# olm-flora-sqw-noRTC.net
KiCad netlist of a schematic drawn in EAGLE
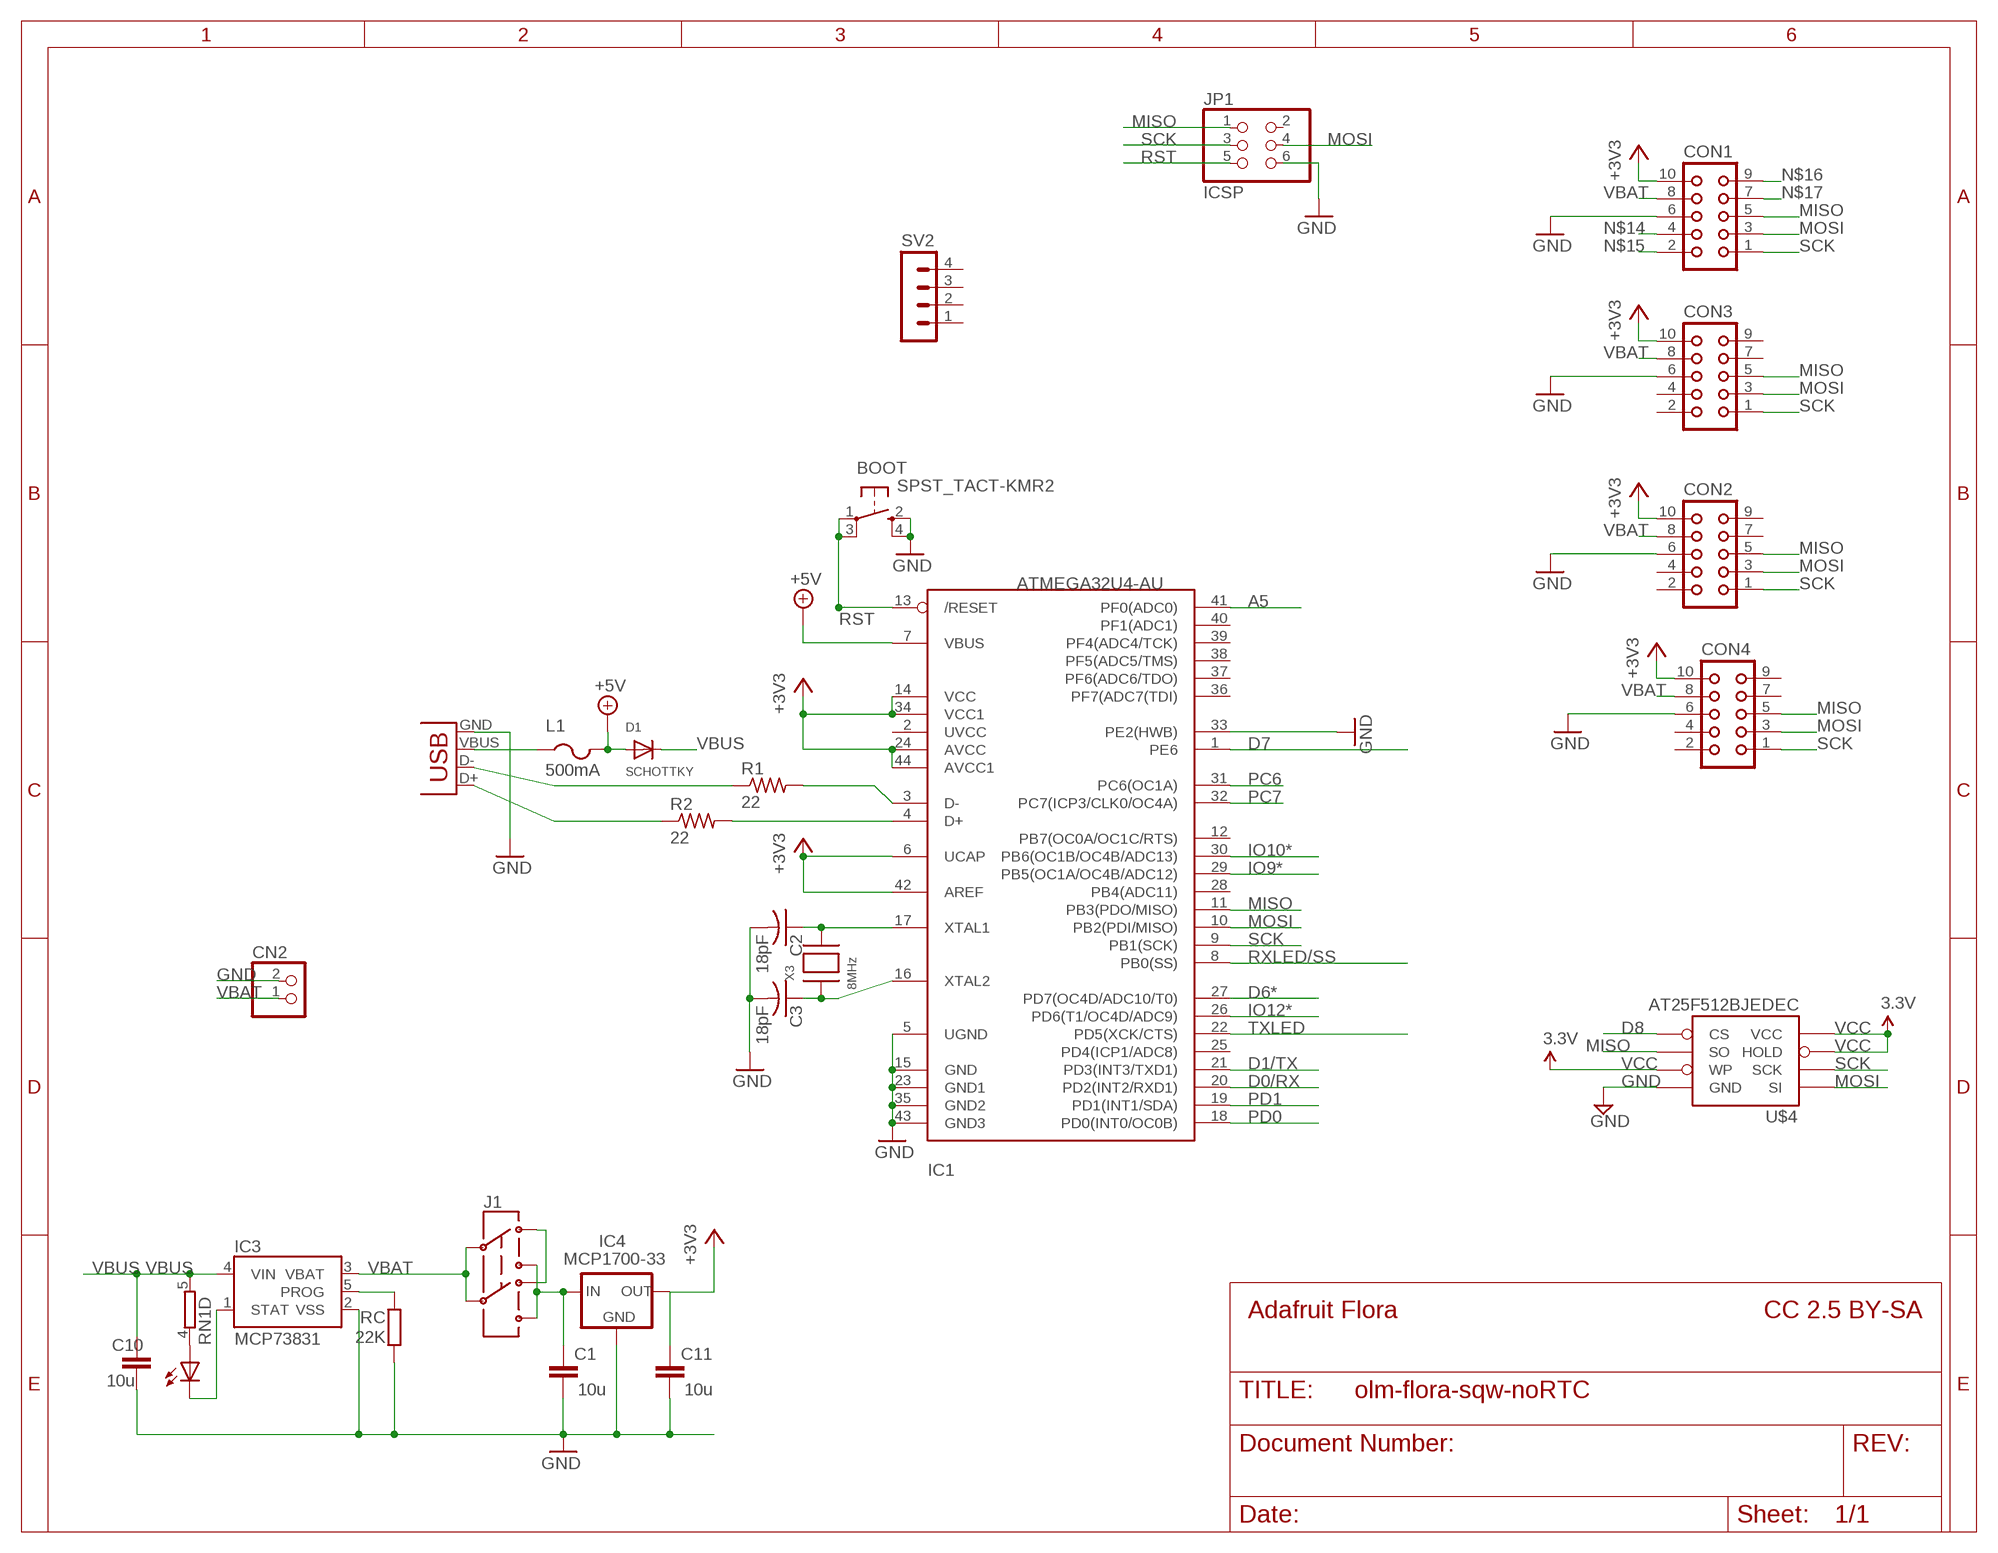
[diagram p0: schematic, sheet 1]

(export (version "E")
  (design (tool "Eeschema 10.0.6"))
  (components
    (comp (ref "BOOT")
      (value "SPST_TACT-KMR2")
      (footprint "eagle-import:KMR2")
      (libsource (lib "eagle-import") (part "SPST_TACT-KMR2"))
    )
    (comp (ref "C1")
      (value "10u")
      (footprint "eagle-import:C0805")
      (libsource (lib "eagle-import") (part "C-EUC0805"))
    )
    (comp (ref "C2")
      (value "18pF")
      (footprint "eagle-import:C0805K")
      (libsource (lib "eagle-import") (part "C-USC0805K"))
    )
    (comp (ref "C3")
      (value "18pF")
      (footprint "eagle-import:C0805K")
      (libsource (lib "eagle-import") (part "C-USC0805K"))
    )
    (comp (ref "C10")
      (value "10u")
      (footprint "eagle-import:C0805")
      (libsource (lib "eagle-import") (part "C-EUC0805"))
    )
    (comp (ref "C11")
      (value "10u")
      (footprint "eagle-import:C0805")
      (libsource (lib "eagle-import") (part "C-EUC0805"))
    )
    (comp (ref "CHG")
      (value "0805")
      (footprint "eagle-import:CHIPLED_0805")
      (libsource (lib "eagle-import") (part "LEDCHIPLED_0805"))
    )
    (comp (ref "CN2")
      (value "JST_2PIN-SMT-RA")
      (footprint "eagle-import:JST-PH-2-SMT-RA")
      (libsource (lib "eagle-import") (part "JST_2PIN-SMT-RA"))
    )
    (comp (ref "CON1")
      (value "CON10")
      (footprint "eagle-import:CON10")
      (libsource (lib "eagle-import") (part "CON10"))
    )
    (comp (ref "CON2")
      (value "CON10")
      (footprint "eagle-import:CON10")
      (libsource (lib "eagle-import") (part "CON10"))
    )
    (comp (ref "CON3")
      (value "CON10")
      (footprint "eagle-import:CON10")
      (libsource (lib "eagle-import") (part "CON10"))
    )
    (comp (ref "CON4")
      (value "CON10")
      (footprint "eagle-import:CON10")
      (libsource (lib "eagle-import") (part "CON10"))
    )
    (comp (ref "D1")
      (value "SCHOTTKY")
      (footprint "eagle-import:SOD-123")
      (libsource (lib "eagle-import") (part "DIODESOD-123"))
    )
    (comp (ref "IC1")
      (value "ATMEGA32U4-AU")
      (footprint "eagle-import:TQFP44")
      (libsource (lib "eagle-import") (part "ATMEGA32U4-AU"))
    )
    (comp (ref "IC3")
      (value "MCP73831")
      (footprint "eagle-import:SOT23-5")
      (libsource (lib "eagle-import") (part "MCP73831"))
    )
    (comp (ref "IC4")
      (value "MCP1700-33")
      (footprint "eagle-import:SOT23")
      (libsource (lib "eagle-import") (part "MCP1700SOT233"))
    )
    (comp (ref "J1")
      (value "AYZ0202")
      (footprint "eagle-import:AYZ0202")
      (libsource (lib "eagle-import") (part "AYZ0202"))
    )
    (comp (ref "JP1")
      (value "ICSP")
      (footprint "eagle-import:2X03")
      (libsource (lib "eagle-import") (part "PINHD-2X3"))
    )
    (comp (ref "L1")
      (value "500mA")
      (footprint "eagle-import:R1206")
      (libsource (lib "eagle-import") (part "PTCFUSE-1206"))
    )
    (comp (ref "R1")
      (value "22")
      (footprint "eagle-import:R0805")
      (libsource (lib "eagle-import") (part "R-US_R0805"))
    )
    (comp (ref "R2")
      (value "22")
      (footprint "eagle-import:R0805")
      (libsource (lib "eagle-import") (part "R-US_R0805"))
    )
    (comp (ref "RC")
      (value "22K")
      (footprint "eagle-import:R0805")
      (libsource (lib "eagle-import") (part "R-EU_R0805"))
    )
    (comp (ref "RN1")
      (value "4R-NEXB38V")
      (footprint "eagle-import:EXB38V")
      (libsource (lib "eagle-import") (part "4R-NEXB38V"))
    )
    (comp (ref "SV2")
      (value "MA04-1")
      (footprint "eagle-import:MA04-1")
      (libsource (lib "eagle-import") (part "MA04-1"))
    )
    (comp (ref "U$4")
      (value "AT25F512BJEDEC")
      (footprint "eagle-import:SO08")
      (libsource (lib "eagle-import") (part "AT25F512BJEDEC"))
    )
    (comp (ref "X1")
      (value "USBSMD")
      (footprint "eagle-import:USB-MINIB")
      (libsource (lib "eagle-import") (part "USBSMD"))
    )
    (comp (ref "X3")
      (value "8MHz")
      (footprint "eagle-import:NX5032")
      (libsource (lib "eagle-import") (part "XTALNX5032"))
    )
  )
  (nets
    (net (code "1") (name "+3V3") (class "Default")
      (node (ref "C11") (pin "1") (pinfunction "1_1") (pintype "passive"))
      (node (ref "CON1") (pin "10") (pinfunction "10_10") (pintype "passive"))
      (node (ref "CON2") (pin "10") (pinfunction "10_10") (pintype "passive"))
      (node (ref "CON3") (pin "10") (pinfunction "10_10") (pintype "passive"))
      (node (ref "CON4") (pin "10") (pinfunction "10_10") (pintype "passive"))
      (node (ref "IC1") (pin "14") (pinfunction "VCC_14") (pintype "bidirectional"))
      (node (ref "IC1") (pin "24") (pinfunction "AVCC_24") (pintype "bidirectional"))
      (node (ref "IC1") (pin "34") (pinfunction "VCC1_34") (pintype "bidirectional"))
      (node (ref "IC1") (pin "42") (pinfunction "AREF_42") (pintype "bidirectional"))
      (node (ref "IC1") (pin "44") (pinfunction "AVCC1_44") (pintype "bidirectional"))
      (node (ref "IC1") (pin "6") (pinfunction "UCAP_6") (pintype "bidirectional"))
      (node (ref "IC4") (pin "2") (pinfunction "OUT_2") (pintype "passive"))
    )
    (net (code "2") (name "+5V") (class "Default")
      (node (ref "D1") (pin "A") (pinfunction "A_A") (pintype "passive"))
      (node (ref "IC1") (pin "7") (pinfunction "VBUS_7") (pintype "bidirectional"))
      (node (ref "L1") (pin "2") (pinfunction "2_2") (pintype "passive"))
    )
    (net (code "3") (name "/A5") (class "Default")
      (node (ref "IC1") (pin "41") (pinfunction "PF0(ADC0)_41") (pintype "bidirectional"))
    )
    (net (code "4") (name "/D0{slash}RX") (class "Default")
      (node (ref "IC1") (pin "20") (pinfunction "PD2(INT2/RXD1)_20") (pintype "bidirectional"))
    )
    (net (code "5") (name "/D1{slash}TX") (class "Default")
      (node (ref "IC1") (pin "21") (pinfunction "PD3(INT3/TXD1)_21") (pintype "bidirectional"))
    )
    (net (code "6") (name "/D6*") (class "Default")
      (node (ref "IC1") (pin "27") (pinfunction "PD7(OC4D/ADC10/T0)_27") (pintype "bidirectional"))
    )
    (net (code "7") (name "/D7") (class "Default")
      (node (ref "IC1") (pin "1") (pinfunction "PE6_1") (pintype "bidirectional"))
    )
    (net (code "8") (name "/D8") (class "Default")
      (node (ref "U$4") (pin "1_CS") (pinfunction "CS_1_CS") (pintype "bidirectional"))
    )
    (net (code "9") (name "/IO9*") (class "Default")
      (node (ref "IC1") (pin "29") (pinfunction "PB5(OC1A/OC4B/ADC12)_29") (pintype "bidirectional"))
    )
    (net (code "10") (name "/IO10*") (class "Default")
      (node (ref "IC1") (pin "30") (pinfunction "PB6(OC1B/OC4B/ADC13)_30") (pintype "bidirectional"))
    )
    (net (code "11") (name "/IO12*") (class "Default")
      (node (ref "IC1") (pin "26") (pinfunction "PD6(T1/OC4D/ADC9)_26") (pintype "bidirectional"))
    )
    (net (code "12") (name "/MISO") (class "Default")
      (node (ref "CON1") (pin "5") (pinfunction "5_5") (pintype "passive"))
      (node (ref "CON2") (pin "5") (pinfunction "5_5") (pintype "passive"))
      (node (ref "CON3") (pin "5") (pinfunction "5_5") (pintype "passive"))
      (node (ref "CON4") (pin "5") (pinfunction "5_5") (pintype "passive"))
      (node (ref "IC1") (pin "11") (pinfunction "PB3(PDO/MISO)_11") (pintype "bidirectional"))
      (node (ref "JP1") (pin "1") (pinfunction "1_1") (pintype "passive"))
      (node (ref "U$4") (pin "2_SO") (pinfunction "SO_2_SO") (pintype "bidirectional"))
    )
    (net (code "13") (name "/MOSI") (class "Default")
      (node (ref "CON1") (pin "3") (pinfunction "3_3") (pintype "passive"))
      (node (ref "CON2") (pin "3") (pinfunction "3_3") (pintype "passive"))
      (node (ref "CON3") (pin "3") (pinfunction "3_3") (pintype "passive"))
      (node (ref "CON4") (pin "3") (pinfunction "3_3") (pintype "passive"))
      (node (ref "IC1") (pin "10") (pinfunction "PB2(PDI/MISO)_10") (pintype "bidirectional"))
      (node (ref "JP1") (pin "4") (pinfunction "4_4") (pintype "passive"))
      (node (ref "U$4") (pin "5_SI") (pinfunction "SI_5_SI") (pintype "bidirectional"))
    )
    (net (code "14") (name "/N$14") (class "Default")
      (node (ref "CON1") (pin "4") (pinfunction "4_4") (pintype "passive"))
    )
    (net (code "15") (name "/N$15") (class "Default")
      (node (ref "CON1") (pin "2") (pinfunction "2_2") (pintype "passive"))
    )
    (net (code "16") (name "/N$16") (class "Default")
      (node (ref "CON1") (pin "9") (pinfunction "9_9") (pintype "passive"))
    )
    (net (code "17") (name "/N$17") (class "Default")
      (node (ref "CON1") (pin "7") (pinfunction "7_7") (pintype "passive"))
    )
    (net (code "18") (name "/PC6") (class "Default")
      (node (ref "IC1") (pin "31") (pinfunction "PC6(OC1A)_31") (pintype "bidirectional"))
    )
    (net (code "19") (name "/PC7") (class "Default")
      (node (ref "IC1") (pin "32") (pinfunction "PC7(ICP3/CLK0/OC4A)_32") (pintype "bidirectional"))
    )
    (net (code "20") (name "/PD0") (class "Default")
      (node (ref "IC1") (pin "18") (pinfunction "PD0(INT0/OC0B)_18") (pintype "bidirectional"))
    )
    (net (code "21") (name "/PD1") (class "Default")
      (node (ref "IC1") (pin "19") (pinfunction "PD1(INT1/SDA)_19") (pintype "bidirectional"))
    )
    (net (code "22") (name "/RST") (class "Default")
      (node (ref "BOOT") (pin "1") (pinfunction "P_1") (pintype "passive"))
      (node (ref "BOOT") (pin "3") (pinfunction "P1_3") (pintype "passive"))
      (node (ref "IC1") (pin "13") (pinfunction "/RESET_13") (pintype "bidirectional"))
      (node (ref "JP1") (pin "5") (pinfunction "5_5") (pintype "passive"))
    )
    (net (code "23") (name "/RXLED{slash}SS") (class "Default")
      (node (ref "IC1") (pin "8") (pinfunction "PB0(SS)_8") (pintype "bidirectional"))
    )
    (net (code "24") (name "/SCK") (class "Default")
      (node (ref "CON1") (pin "1") (pinfunction "1_1") (pintype "passive"))
      (node (ref "CON2") (pin "1") (pinfunction "1_1") (pintype "passive"))
      (node (ref "CON3") (pin "1") (pinfunction "1_1") (pintype "passive"))
      (node (ref "CON4") (pin "1") (pinfunction "1_1") (pintype "passive"))
      (node (ref "IC1") (pin "9") (pinfunction "PB1(SCK)_9") (pintype "bidirectional"))
      (node (ref "JP1") (pin "3") (pinfunction "3_3") (pintype "passive"))
      (node (ref "U$4") (pin "6_SCK") (pinfunction "SCK_6_SCK") (pintype "bidirectional"))
    )
    (net (code "25") (name "/TXLED") (class "Default")
      (node (ref "IC1") (pin "22") (pinfunction "PD5(XCK/CTS)_22") (pintype "bidirectional"))
    )
    (net (code "26") (name "/VBAT") (class "Default")
      (node (ref "CN2") (pin "1") (pinfunction "2_1") (pintype "passive"))
      (node (ref "CON1") (pin "8") (pinfunction "8_8") (pintype "passive"))
      (node (ref "CON2") (pin "8") (pinfunction "8_8") (pintype "passive"))
      (node (ref "CON3") (pin "8") (pinfunction "8_8") (pintype "passive"))
      (node (ref "CON4") (pin "8") (pinfunction "8_8") (pintype "passive"))
      (node (ref "IC3") (pin "3") (pinfunction "VBAT_3") (pintype "power_in"))
      (node (ref "J1") (pin "2") (pinfunction "2_2") (pintype "bidirectional"))
      (node (ref "J1") (pin "5") (pinfunction "5_5") (pintype "bidirectional"))
    )
    (net (code "27") (name "/VBUS") (class "Default")
      (node (ref "C10") (pin "1") (pinfunction "1_1") (pintype "passive"))
      (node (ref "D1") (pin "C") (pinfunction "C_C") (pintype "passive"))
      (node (ref "IC3") (pin "4") (pinfunction "VIN_4") (pintype "power_in"))
      (node (ref "L1") (pin "1") (pinfunction "1_1") (pintype "passive"))
      (node (ref "RN1") (pin "5") (pinfunction "2_5") (pintype "passive"))
      (node (ref "X1") (pin "VBUS") (pinfunction "VBUS_VBUS") (pintype "bidirectional"))
    )
    (net (code "28") (name "3.3V") (class "Default")
      (node (ref "U$4") (pin "3_WP") (pinfunction "WP_3_WP") (pintype "bidirectional"))
      (node (ref "U$4") (pin "7_HOLD") (pinfunction "HOLD_7_HOLD") (pintype "bidirectional"))
      (node (ref "U$4") (pin "8_VCC") (pinfunction "VCC_8_VCC") (pintype "bidirectional"))
    )
    (net (code "29") (name "GND") (class "Default")
      (node (ref "BOOT") (pin "2") (pinfunction "S_2") (pintype "passive"))
      (node (ref "BOOT") (pin "4") (pinfunction "S1_4") (pintype "passive"))
      (node (ref "C1") (pin "2") (pinfunction "2_2") (pintype "passive"))
      (node (ref "C10") (pin "2") (pinfunction "2_2") (pintype "passive"))
      (node (ref "C11") (pin "2") (pinfunction "2_2") (pintype "passive"))
      (node (ref "C2") (pin "2") (pinfunction "2_2") (pintype "passive"))
      (node (ref "C3") (pin "2") (pinfunction "2_2") (pintype "passive"))
      (node (ref "CN2") (pin "2") (pinfunction "1_2") (pintype "passive"))
      (node (ref "CON1") (pin "6") (pinfunction "6_6") (pintype "passive"))
      (node (ref "CON2") (pin "6") (pinfunction "6_6") (pintype "passive"))
      (node (ref "CON3") (pin "6") (pinfunction "6_6") (pintype "passive"))
      (node (ref "CON4") (pin "6") (pinfunction "6_6") (pintype "passive"))
      (node (ref "IC1") (pin "15") (pinfunction "GND_15") (pintype "bidirectional"))
      (node (ref "IC1") (pin "23") (pinfunction "GND1_23") (pintype "bidirectional"))
      (node (ref "IC1") (pin "33") (pinfunction "PE2(HWB)_33") (pintype "bidirectional"))
      (node (ref "IC1") (pin "35") (pinfunction "GND2_35") (pintype "bidirectional"))
      (node (ref "IC1") (pin "43") (pinfunction "GND3_43") (pintype "bidirectional"))
      (node (ref "IC1") (pin "5") (pinfunction "UGND_5") (pintype "bidirectional"))
      (node (ref "IC3") (pin "2") (pinfunction "VSS_2") (pintype "power_in"))
      (node (ref "IC4") (pin "1") (pinfunction "GND_1") (pintype "input"))
      (node (ref "JP1") (pin "6") (pinfunction "6_6") (pintype "passive"))
      (node (ref "RC") (pin "1") (pinfunction "1_1") (pintype "passive"))
      (node (ref "U$4") (pin "4_GND") (pinfunction "GND_4_GND") (pintype "bidirectional"))
      (node (ref "X1") (pin "GND") (pinfunction "GND_GND") (pintype "bidirectional"))
    )
    (net (code "30") (name "Net-(IC1-D+)") (class "Default")
      (node (ref "IC1") (pin "4") (pinfunction "D+_4") (pintype "bidirectional"))
      (node (ref "R2") (pin "2") (pinfunction "2_2") (pintype "passive"))
    )
    (net (code "31") (name "Net-(IC1-D-)") (class "Default")
      (node (ref "IC1") (pin "3") (pinfunction "D-_3") (pintype "bidirectional"))
      (node (ref "R1") (pin "2") (pinfunction "2_2") (pintype "passive"))
    )
    (net (code "32") (name "Net-(IC1-XTAL1)") (class "Default")
      (node (ref "C2") (pin "1") (pinfunction "1_1") (pintype "passive"))
      (node (ref "IC1") (pin "17") (pinfunction "XTAL1_17") (pintype "bidirectional"))
      (node (ref "X3") (pin "P$2") (pinfunction "P$2_P$2") (pintype "bidirectional"))
    )
    (net (code "33") (name "Net-(IC1-XTAL2)") (class "Default")
      (node (ref "C3") (pin "1") (pinfunction "1_1") (pintype "passive"))
      (node (ref "IC1") (pin "16") (pinfunction "XTAL2_16") (pintype "bidirectional"))
      (node (ref "X3") (pin "P$1") (pinfunction "P$1_P$1") (pintype "bidirectional"))
    )
    (net (code "34") (name "Net-(IC3-PROG)") (class "Default")
      (node (ref "IC3") (pin "5") (pinfunction "PROG_5") (pintype "input"))
      (node (ref "RC") (pin "2") (pinfunction "2_2") (pintype "passive"))
    )
    (net (code "35") (name "Net-(IC3-STAT)") (class "Default")
      (node (ref "CHG") (pin "C") (pinfunction "C_C") (pintype "passive"))
      (node (ref "IC3") (pin "1") (pinfunction "STAT_1") (pintype "output"))
    )
    (net (code "36") (name "Net-(IC4-IN)") (class "Default")
      (node (ref "C1") (pin "1") (pinfunction "1_1") (pintype "passive"))
      (node (ref "IC4") (pin "3") (pinfunction "IN_3") (pintype "input"))
      (node (ref "J1") (pin "1") (pinfunction "3_1") (pintype "bidirectional"))
      (node (ref "J1") (pin "4") (pinfunction "6_4") (pintype "bidirectional"))
    )
    (net (code "37") (name "Net-(J1-1)") (class "Default")
      (node (ref "J1") (pin "3") (pinfunction "1_3") (pintype "bidirectional"))
      (node (ref "J1") (pin "6") (pinfunction "4_6") (pintype "bidirectional"))
    )
    (net (code "38") (name "Net-(R1-Pad1)") (class "Default")
      (node (ref "R1") (pin "1") (pinfunction "1_1") (pintype "passive"))
      (node (ref "X1") (pin "D-") (pinfunction "D-_D-") (pintype "bidirectional"))
    )
    (net (code "39") (name "Net-(R2-Pad1)") (class "Default")
      (node (ref "R2") (pin "1") (pinfunction "1_1") (pintype "passive"))
      (node (ref "X1") (pin "D+") (pinfunction "D+_D+") (pintype "bidirectional"))
    )
    (net (code "40") (name "Net-(RN1D-1)") (class "Default")
      (node (ref "CHG") (pin "A") (pinfunction "A_A") (pintype "passive"))
      (node (ref "RN1") (pin "4") (pinfunction "1_4") (pintype "passive"))
    )
    (net (code "41") (name "unconnected-(CON2-Pad2)") (class "Default")
      (node (ref "CON2") (pin "2") (pinfunction "2_2") (pintype "passive"))
    )
    (net (code "42") (name "unconnected-(CON2-Pad4)") (class "Default")
      (node (ref "CON2") (pin "4") (pinfunction "4_4") (pintype "passive"))
    )
    (net (code "43") (name "unconnected-(CON2-Pad7)") (class "Default")
      (node (ref "CON2") (pin "7") (pinfunction "7_7") (pintype "passive"))
    )
    (net (code "44") (name "unconnected-(CON2-Pad9)") (class "Default")
      (node (ref "CON2") (pin "9") (pinfunction "9_9") (pintype "passive"))
    )
    (net (code "45") (name "unconnected-(CON3-Pad2)") (class "Default")
      (node (ref "CON3") (pin "2") (pinfunction "2_2") (pintype "passive"))
    )
    (net (code "46") (name "unconnected-(CON3-Pad4)") (class "Default")
      (node (ref "CON3") (pin "4") (pinfunction "4_4") (pintype "passive"))
    )
    (net (code "47") (name "unconnected-(CON3-Pad7)") (class "Default")
      (node (ref "CON3") (pin "7") (pinfunction "7_7") (pintype "passive"))
    )
    (net (code "48") (name "unconnected-(CON3-Pad9)") (class "Default")
      (node (ref "CON3") (pin "9") (pinfunction "9_9") (pintype "passive"))
    )
    (net (code "49") (name "unconnected-(CON4-Pad2)") (class "Default")
      (node (ref "CON4") (pin "2") (pinfunction "2_2") (pintype "passive"))
    )
    (net (code "50") (name "unconnected-(CON4-Pad4)") (class "Default")
      (node (ref "CON4") (pin "4") (pinfunction "4_4") (pintype "passive"))
    )
    (net (code "51") (name "unconnected-(CON4-Pad7)") (class "Default")
      (node (ref "CON4") (pin "7") (pinfunction "7_7") (pintype "passive"))
    )
    (net (code "52") (name "unconnected-(CON4-Pad9)") (class "Default")
      (node (ref "CON4") (pin "9") (pinfunction "9_9") (pintype "passive"))
    )
    (net (code "53") (name "unconnected-(IC1-PB4(ADC11)-Pad28)") (class "Default")
      (node (ref "IC1") (pin "28") (pinfunction "PB4(ADC11)_28") (pintype "bidirectional"))
    )
    (net (code "54") (name "unconnected-(IC1-PB7(OC0A{slash}OC1C{slash}RTS)-Pad12)") (class "Default")
      (node (ref "IC1") (pin "12") (pinfunction "PB7(OC0A/OC1C/RTS)_12") (pintype "bidirectional"))
    )
    (net (code "55") (name "unconnected-(IC1-PD4(ICP1{slash}ADC8)-Pad25)") (class "Default")
      (node (ref "IC1") (pin "25") (pinfunction "PD4(ICP1/ADC8)_25") (pintype "bidirectional"))
    )
    (net (code "56") (name "unconnected-(IC1-PF1(ADC1)-Pad40)") (class "Default")
      (node (ref "IC1") (pin "40") (pinfunction "PF1(ADC1)_40") (pintype "bidirectional"))
    )
    (net (code "57") (name "unconnected-(IC1-PF4(ADC4{slash}TCK)-Pad39)") (class "Default")
      (node (ref "IC1") (pin "39") (pinfunction "PF4(ADC4/TCK)_39") (pintype "bidirectional"))
    )
    (net (code "58") (name "unconnected-(IC1-PF5(ADC5{slash}TMS)-Pad38)") (class "Default")
      (node (ref "IC1") (pin "38") (pinfunction "PF5(ADC5/TMS)_38") (pintype "bidirectional"))
    )
    (net (code "59") (name "unconnected-(IC1-PF6(ADC6{slash}TDO)-Pad37)") (class "Default")
      (node (ref "IC1") (pin "37") (pinfunction "PF6(ADC6/TDO)_37") (pintype "bidirectional"))
    )
    (net (code "60") (name "unconnected-(IC1-PF7(ADC7(TDI)-Pad36)") (class "Default")
      (node (ref "IC1") (pin "36") (pinfunction "PF7(ADC7(TDI)_36") (pintype "bidirectional"))
    )
    (net (code "61") (name "unconnected-(IC1-UVCC-Pad2)") (class "Default")
      (node (ref "IC1") (pin "2") (pinfunction "UVCC_2") (pintype "bidirectional"))
    )
    (net (code "62") (name "unconnected-(JP1-Pad2)") (class "Default")
      (node (ref "JP1") (pin "2") (pinfunction "2_2") (pintype "passive"))
    )
    (net (code "63") (name "unconnected-(SV2-Pad1)") (class "Default")
      (node (ref "SV2") (pin "1") (pinfunction "1_1") (pintype "passive"))
    )
    (net (code "64") (name "unconnected-(SV2-Pad2)") (class "Default")
      (node (ref "SV2") (pin "2") (pinfunction "2_2") (pintype "passive"))
    )
    (net (code "65") (name "unconnected-(SV2-Pad3)") (class "Default")
      (node (ref "SV2") (pin "3") (pinfunction "3_3") (pintype "passive"))
    )
    (net (code "66") (name "unconnected-(SV2-Pad4)") (class "Default")
      (node (ref "SV2") (pin "4") (pinfunction "4_4") (pintype "passive"))
    )
  )
)
